# PCB-Neopixel_Control.net
KiCad netlist of a schematic drawn in EAGLE
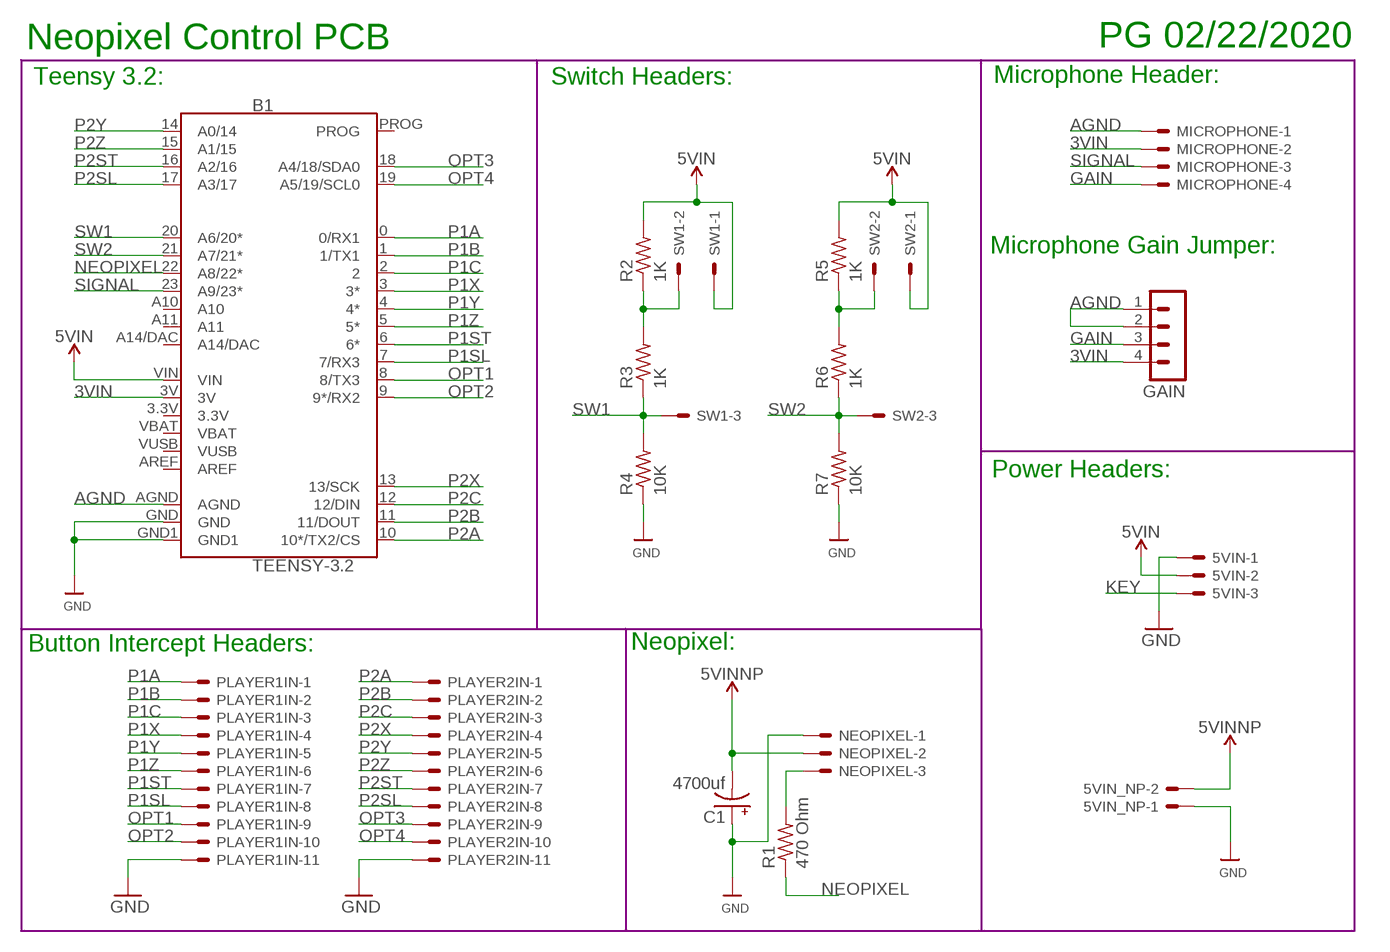
[diagram p0: schematic, sheet 1]

(export (version "E")
  (design (tool "Eeschema 10.0.6"))
  (components
    (comp (ref "5VIN")
      (value "KK-156-3")
      (footprint "eagle-import:KK-156-3")
      (fields (field (name "MF") "MOLEX"))
      (libsource (lib "eagle-import") (part "KK-156-3"))
    )
    (comp (ref "5VIN_NP")
      (value "KK-156-2")
      (footprint "eagle-import:KK-156-2")
      (fields (field (name "MF") "MOLEX"))
      (libsource (lib "eagle-import") (part "KK-156-2"))
    )
    (comp (ref "B1")
      (value "TEENSY-3.2")
      (footprint "eagle-import:TEENSY-3.1")
      (libsource (lib "eagle-import") (part "TEENSY-3.1SILK"))
    )
    (comp (ref "C1")
      (value "4700uf")
      (footprint "eagle-import:E5-13")
      (libsource (lib "eagle-import") (part "CPOL-USE5-13"))
    )
    (comp (ref "GAIN")
      (value "MA04-1")
      (footprint "eagle-import:MA04-1")
      (libsource (lib "eagle-import") (part "MA04-1"))
    )
    (comp (ref "MICROPHONE")
      (value "KK-156-4")
      (footprint "eagle-import:KK-156-4")
      (fields (field (name "MF") "MOLEX"))
      (libsource (lib "eagle-import") (part "KK-156-4"))
    )
    (comp (ref "NEOPIXEL")
      (value "KK-156-3")
      (footprint "eagle-import:KK-156-3")
      (fields (field (name "MF") "MOLEX"))
      (libsource (lib "eagle-import") (part "KK-156-3"))
    )
    (comp (ref "PLAYER1IN")
      (value "KK-156-11")
      (footprint "eagle-import:KK-156-11")
      (fields (field (name "MF") "MOLEX"))
      (libsource (lib "eagle-import") (part "KK-156-11"))
    )
    (comp (ref "PLAYER2IN")
      (value "KK-156-11")
      (footprint "eagle-import:KK-156-11")
      (fields (field (name "MF") "MOLEX"))
      (libsource (lib "eagle-import") (part "KK-156-11"))
    )
    (comp (ref "R1")
      (value "470 Ohm")
      (footprint "eagle-import:R1206")
      (libsource (lib "eagle-import") (part "R-US_R1206"))
    )
    (comp (ref "R2")
      (value "1K")
      (footprint "eagle-import:R1206")
      (libsource (lib "eagle-import") (part "R-US_R1206"))
    )
    (comp (ref "R3")
      (value "1K")
      (footprint "eagle-import:R1206")
      (libsource (lib "eagle-import") (part "R-US_R1206"))
    )
    (comp (ref "R4")
      (value "10K")
      (footprint "eagle-import:R1206")
      (libsource (lib "eagle-import") (part "R-US_R1206"))
    )
    (comp (ref "R5")
      (value "1K")
      (footprint "eagle-import:R1206")
      (libsource (lib "eagle-import") (part "R-US_R1206"))
    )
    (comp (ref "R6")
      (value "1K")
      (footprint "eagle-import:R1206")
      (libsource (lib "eagle-import") (part "R-US_R1206"))
    )
    (comp (ref "R7")
      (value "10K")
      (footprint "eagle-import:R1206")
      (libsource (lib "eagle-import") (part "R-US_R1206"))
    )
    (comp (ref "SW1")
      (value "KK-156-3")
      (footprint "eagle-import:KK-156-3")
      (fields (field (name "MF") "MOLEX"))
      (libsource (lib "eagle-import") (part "KK-156-3"))
    )
    (comp (ref "SW2")
      (value "KK-156-3")
      (footprint "eagle-import:KK-156-3")
      (fields (field (name "MF") "MOLEX"))
      (libsource (lib "eagle-import") (part "KK-156-3"))
    )
  )
  (nets
    (net (code "1") (name "/3.3V") (class "Default")
      (node (ref "B1") (pin "3.3V") (pinfunction "3.3V_3.3V") (pintype "power_in"))
    )
    (net (code "2") (name "/3VIN") (class "Default")
      (node (ref "B1") (pin "3V") (pinfunction "3V_3V") (pintype "power_in"))
      (node (ref "GAIN") (pin "4") (pinfunction "4_4") (pintype "passive"))
      (node (ref "MICROPHONE") (pin "2") (pinfunction "S_2") (pintype "passive"))
    )
    (net (code "3") (name "/AGND") (class "Default")
      (node (ref "B1") (pin "AGND") (pinfunction "AGND_AGND") (pintype "power_in"))
      (node (ref "GAIN") (pin "1") (pinfunction "1_1") (pintype "passive"))
      (node (ref "GAIN") (pin "2") (pinfunction "2_2") (pintype "passive"))
      (node (ref "MICROPHONE") (pin "1") (pinfunction "S_1") (pintype "passive"))
    )
    (net (code "4") (name "/GAIN") (class "Default")
      (node (ref "GAIN") (pin "3") (pinfunction "3_3") (pintype "passive"))
      (node (ref "MICROPHONE") (pin "4") (pinfunction "S_4") (pintype "passive"))
    )
    (net (code "5") (name "/KEY") (class "Default")
      (node (ref "5VIN") (pin "3") (pinfunction "S_3") (pintype "passive"))
    )
    (net (code "6") (name "/NEOPIXEL") (class "Default")
      (node (ref "B1") (pin "22") (pinfunction "A8/22*_22") (pintype "bidirectional"))
      (node (ref "R1") (pin "1") (pinfunction "1_1") (pintype "passive"))
    )
    (net (code "7") (name "/OPT1") (class "Default")
      (node (ref "B1") (pin "8") (pinfunction "8/TX3_8") (pintype "bidirectional"))
      (node (ref "PLAYER1IN") (pin "9") (pinfunction "S_9") (pintype "passive"))
    )
    (net (code "8") (name "/OPT2") (class "Default")
      (node (ref "B1") (pin "9") (pinfunction "9*/RX2_9") (pintype "bidirectional"))
      (node (ref "PLAYER1IN") (pin "10") (pinfunction "S_10") (pintype "passive"))
    )
    (net (code "9") (name "/OPT3") (class "Default")
      (node (ref "B1") (pin "18") (pinfunction "A4/18/SDA0_18") (pintype "bidirectional"))
      (node (ref "PLAYER2IN") (pin "9") (pinfunction "S_9") (pintype "passive"))
    )
    (net (code "10") (name "/OPT4") (class "Default")
      (node (ref "B1") (pin "19") (pinfunction "A5/19/SCL0_19") (pintype "bidirectional"))
      (node (ref "PLAYER2IN") (pin "10") (pinfunction "S_10") (pintype "passive"))
    )
    (net (code "11") (name "/P1A") (class "Default")
      (node (ref "B1") (pin "0") (pinfunction "0/RX1_0") (pintype "bidirectional"))
      (node (ref "PLAYER1IN") (pin "1") (pinfunction "S_1") (pintype "passive"))
    )
    (net (code "12") (name "/P1B") (class "Default")
      (node (ref "B1") (pin "1") (pinfunction "1/TX1_1") (pintype "bidirectional"))
      (node (ref "PLAYER1IN") (pin "2") (pinfunction "S_2") (pintype "passive"))
    )
    (net (code "13") (name "/P1C") (class "Default")
      (node (ref "B1") (pin "2") (pinfunction "2_2") (pintype "bidirectional"))
      (node (ref "PLAYER1IN") (pin "3") (pinfunction "S_3") (pintype "passive"))
    )
    (net (code "14") (name "/P1SL") (class "Default")
      (node (ref "B1") (pin "7") (pinfunction "7/RX3_7") (pintype "bidirectional"))
      (node (ref "PLAYER1IN") (pin "8") (pinfunction "S_8") (pintype "passive"))
    )
    (net (code "15") (name "/P1ST") (class "Default")
      (node (ref "B1") (pin "6") (pinfunction "6*_6") (pintype "bidirectional"))
      (node (ref "PLAYER1IN") (pin "7") (pinfunction "S_7") (pintype "passive"))
    )
    (net (code "16") (name "/P1X") (class "Default")
      (node (ref "B1") (pin "3") (pinfunction "3*_3") (pintype "bidirectional"))
      (node (ref "PLAYER1IN") (pin "4") (pinfunction "S_4") (pintype "passive"))
    )
    (net (code "17") (name "/P1Y") (class "Default")
      (node (ref "B1") (pin "4") (pinfunction "4*_4") (pintype "bidirectional"))
      (node (ref "PLAYER1IN") (pin "5") (pinfunction "S_5") (pintype "passive"))
    )
    (net (code "18") (name "/P1Z") (class "Default")
      (node (ref "B1") (pin "5") (pinfunction "5*_5") (pintype "bidirectional"))
      (node (ref "PLAYER1IN") (pin "6") (pinfunction "S_6") (pintype "passive"))
    )
    (net (code "19") (name "/P2A") (class "Default")
      (node (ref "B1") (pin "10") (pinfunction "10*/TX2/CS_10") (pintype "bidirectional"))
      (node (ref "PLAYER2IN") (pin "1") (pinfunction "S_1") (pintype "passive"))
    )
    (net (code "20") (name "/P2B") (class "Default")
      (node (ref "B1") (pin "11") (pinfunction "11/DOUT_11") (pintype "bidirectional"))
      (node (ref "PLAYER2IN") (pin "2") (pinfunction "S_2") (pintype "passive"))
    )
    (net (code "21") (name "/P2C") (class "Default")
      (node (ref "B1") (pin "12") (pinfunction "12/DIN_12") (pintype "bidirectional"))
      (node (ref "PLAYER2IN") (pin "3") (pinfunction "S_3") (pintype "passive"))
    )
    (net (code "22") (name "/P2SL") (class "Default")
      (node (ref "B1") (pin "17") (pinfunction "A3/17_17") (pintype "bidirectional"))
      (node (ref "PLAYER2IN") (pin "8") (pinfunction "S_8") (pintype "passive"))
    )
    (net (code "23") (name "/P2ST") (class "Default")
      (node (ref "B1") (pin "16") (pinfunction "A2/16_16") (pintype "bidirectional"))
      (node (ref "PLAYER2IN") (pin "7") (pinfunction "S_7") (pintype "passive"))
    )
    (net (code "24") (name "/P2X") (class "Default")
      (node (ref "B1") (pin "13") (pinfunction "13/SCK_13") (pintype "bidirectional"))
      (node (ref "PLAYER2IN") (pin "4") (pinfunction "S_4") (pintype "passive"))
    )
    (net (code "25") (name "/P2Y") (class "Default")
      (node (ref "B1") (pin "14") (pinfunction "A0/14_14") (pintype "bidirectional"))
      (node (ref "PLAYER2IN") (pin "5") (pinfunction "S_5") (pintype "passive"))
    )
    (net (code "26") (name "/P2Z") (class "Default")
      (node (ref "B1") (pin "15") (pinfunction "A1/15_15") (pintype "bidirectional"))
      (node (ref "PLAYER2IN") (pin "6") (pinfunction "S_6") (pintype "passive"))
    )
    (net (code "27") (name "/SIGNAL") (class "Default")
      (node (ref "B1") (pin "23") (pinfunction "A9/23*_23") (pintype "bidirectional"))
      (node (ref "MICROPHONE") (pin "3") (pinfunction "S_3") (pintype "passive"))
    )
    (net (code "28") (name "/SW1") (class "Default")
      (node (ref "B1") (pin "20") (pinfunction "A6/20*_20") (pintype "bidirectional"))
      (node (ref "R3") (pin "1") (pinfunction "1_1") (pintype "passive"))
      (node (ref "R4") (pin "2") (pinfunction "2_2") (pintype "passive"))
      (node (ref "SW1") (pin "3") (pinfunction "S_3") (pintype "passive"))
    )
    (net (code "29") (name "/SW2") (class "Default")
      (node (ref "B1") (pin "21") (pinfunction "A7/21*_21") (pintype "bidirectional"))
      (node (ref "R6") (pin "1") (pinfunction "1_1") (pintype "passive"))
      (node (ref "R7") (pin "2") (pinfunction "2_2") (pintype "passive"))
      (node (ref "SW2") (pin "3") (pinfunction "S_3") (pintype "passive"))
    )
    (net (code "30") (name "/VBAT") (class "Default")
      (node (ref "B1") (pin "VBAT") (pinfunction "VBAT_VBAT") (pintype "power_in"))
    )
    (net (code "31") (name "/VUSB") (class "Default")
      (node (ref "B1") (pin "VUSB") (pinfunction "VUSB_VUSB") (pintype "power_in"))
    )
    (net (code "32") (name "5VIN") (class "Default")
      (node (ref "5VIN") (pin "2") (pinfunction "S_2") (pintype "passive"))
      (node (ref "B1") (pin "VIN") (pinfunction "VIN_VIN") (pintype "power_in"))
      (node (ref "R2") (pin "2") (pinfunction "2_2") (pintype "passive"))
      (node (ref "R5") (pin "2") (pinfunction "2_2") (pintype "passive"))
      (node (ref "SW1") (pin "1") (pinfunction "S_1") (pintype "passive"))
      (node (ref "SW2") (pin "1") (pinfunction "S_1") (pintype "passive"))
    )
    (net (code "33") (name "5VINNP") (class "Default")
      (node (ref "5VIN_NP") (pin "2") (pinfunction "S_2") (pintype "passive"))
      (node (ref "C1") (pin "-") (pinfunction "-_-") (pintype "passive"))
      (node (ref "NEOPIXEL") (pin "2") (pinfunction "S_2") (pintype "passive"))
    )
    (net (code "34") (name "GND") (class "Default")
      (node (ref "5VIN") (pin "1") (pinfunction "S_1") (pintype "passive"))
      (node (ref "5VIN_NP") (pin "1") (pinfunction "S_1") (pintype "passive"))
      (node (ref "B1") (pin "GND") (pinfunction "GND_GND") (pintype "power_in"))
      (node (ref "B1") (pin "GND1") (pinfunction "GND1_GND1") (pintype "power_in"))
      (node (ref "C1") (pin "+") (pinfunction "+_+") (pintype "passive"))
      (node (ref "NEOPIXEL") (pin "1") (pinfunction "S_1") (pintype "passive"))
      (node (ref "PLAYER1IN") (pin "11") (pinfunction "S_11") (pintype "passive"))
      (node (ref "PLAYER2IN") (pin "11") (pinfunction "S_11") (pintype "passive"))
      (node (ref "R4") (pin "1") (pinfunction "1_1") (pintype "passive"))
      (node (ref "R7") (pin "1") (pinfunction "1_1") (pintype "passive"))
    )
    (net (code "35") (name "Net-(NEOPIXELC-S)") (class "Default")
      (node (ref "NEOPIXEL") (pin "3") (pinfunction "S_3") (pintype "passive"))
      (node (ref "R1") (pin "2") (pinfunction "2_2") (pintype "passive"))
    )
    (net (code "36") (name "Net-(SW1B-S)") (class "Default")
      (node (ref "R2") (pin "1") (pinfunction "1_1") (pintype "passive"))
      (node (ref "R3") (pin "2") (pinfunction "2_2") (pintype "passive"))
      (node (ref "SW1") (pin "2") (pinfunction "S_2") (pintype "passive"))
    )
    (net (code "37") (name "Net-(SW2B-S)") (class "Default")
      (node (ref "R5") (pin "1") (pinfunction "1_1") (pintype "passive"))
      (node (ref "R6") (pin "2") (pinfunction "2_2") (pintype "passive"))
      (node (ref "SW2") (pin "2") (pinfunction "S_2") (pintype "passive"))
    )
    (net (code "38") (name "unconnected-(B1-PadA10)") (class "Default")
      (node (ref "B1") (pin "A10") (pinfunction "A10_A10") (pintype "bidirectional"))
    )
    (net (code "39") (name "unconnected-(B1-PadA11)") (class "Default")
      (node (ref "B1") (pin "A11") (pinfunction "A11_A11") (pintype "bidirectional"))
    )
    (net (code "40") (name "unconnected-(B1-PadA14{slash}DAC)") (class "Default")
      (node (ref "B1") (pin "A14/DAC") (pinfunction "A14/DAC_A14/DAC") (pintype "bidirectional"))
    )
    (net (code "41") (name "unconnected-(B1-PadAREF)") (class "Default")
      (node (ref "B1") (pin "AREF") (pinfunction "AREF_AREF") (pintype "bidirectional"))
    )
    (net (code "42") (name "unconnected-(B1-PadPROG)") (class "Default")
      (node (ref "B1") (pin "PROG") (pinfunction "PROG_PROG") (pintype "bidirectional"))
    )
  )
)
